# ReboostV2_CAN.net
KiCad netlist of a schematic drawn in Altium Designer
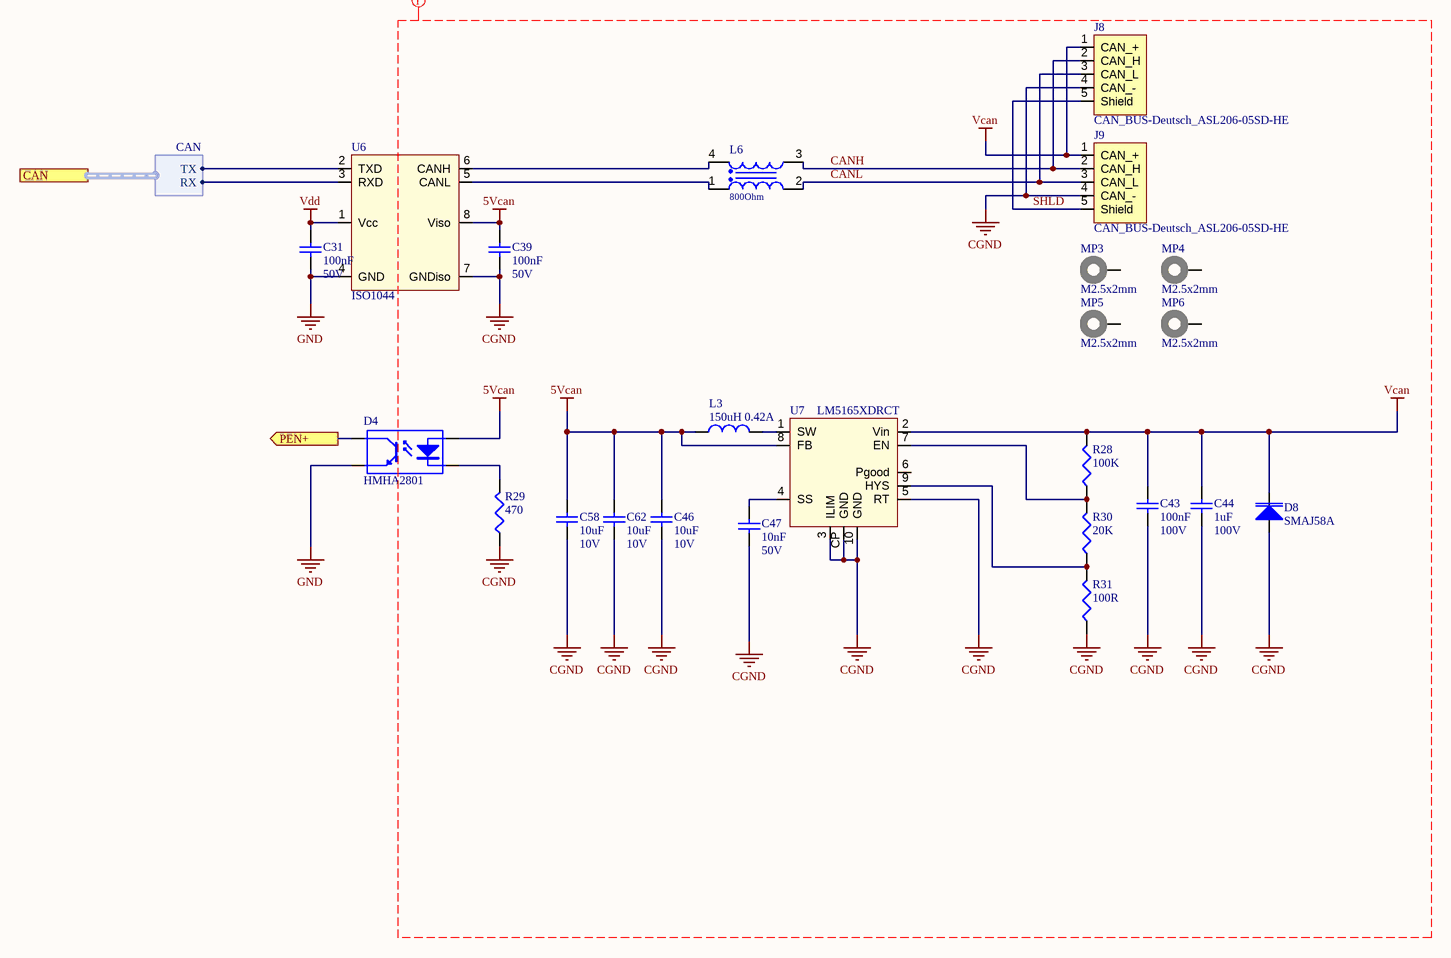
[diagram p0: ReboostV2_CAN.SchDoc]

(export (version "E")
  (design (tool "Eeschema 10.0.6"))
  (components
    (comp (ref "C31")
      (value "100nF")
      (footprint "C0603")
      (description "Capacitor, 100nF, 50V, X7R")
      (fields (field (name "VOLTAGE RATING") "50V"))
      (libsource (lib "AR_Capacitors_Ceramic") (part "100nF/0603/CER/50V"))
    )
    (comp (ref "C39")
      (value "100nF")
      (footprint "C0603")
      (description "Capacitor, 100nF, 50V, X7R")
      (fields (field (name "VOLTAGE RATING") "50V"))
      (libsource (lib "AR_Capacitors_Ceramic") (part "100nF/0603/CER/50V"))
    )
    (comp (ref "C43")
      (value "100nF")
      (footprint "C-0805")
      (description "Capacitor, 100nF, 100V, X7R")
      (fields (field (name "VOLTAGE RATING") "100V"))
      (libsource (lib "AR_Capacitors_Ceramic") (part "100nF/0805/CER/100V"))
    )
    (comp (ref "C44")
      (value "1uF")
      (footprint "C-1206")
      (description "Capacitor, 1uF, 100V, X7R")
      (fields (field (name "VOLTAGE RATING") "100V"))
      (libsource (lib "AR_Capacitors_Ceramic") (part "1uF/1206/CER/100V"))
    )
    (comp (ref "C46")
      (value "10uF")
      (footprint "C-0805")
      (description "Capacitor, 10uF, 10V, X7R")
      (fields (field (name "VOLTAGE RATING") "10V"))
      (libsource (lib "AR_Capacitors_Ceramic") (part "10uF/0805/CER/10V"))
    )
    (comp (ref "C47")
      (value "10nF")
      (footprint "C0603")
      (description "Capacitor, 10nF, 50V, X7R")
      (fields (field (name "VOLTAGE RATING") "50V"))
      (libsource (lib "AR_Capacitors_Ceramic") (part "10nF/0603/CER/50V"))
    )
    (comp (ref "C58")
      (value "10uF")
      (footprint "C-0805")
      (description "Capacitor, 10uF, 10V, X7R")
      (fields (field (name "VOLTAGE RATING") "10V"))
      (libsource (lib "AR_Capacitors_Ceramic") (part "10uF/0805/CER/10V"))
    )
    (comp (ref "C62")
      (value "10uF")
      (footprint "C-0805")
      (description "Capacitor, 10uF, 10V, X7R")
      (fields (field (name "VOLTAGE RATING") "10V"))
      (libsource (lib "AR_Capacitors_Ceramic") (part "10uF/0805/CER/10V"))
    )
    (comp (ref "D4")
      (value "HMHA2801")
      (footprint "FSOP4")
      (description "Optocoupler, Vout:80V, Iin:0.01A")
      (libsource (lib "AR_Optocouplers") (part "HMHA2801"))
    )
    (comp (ref "D8")
      (value "SMAJ58A")
      (footprint "SMA")
      (description "Diode TVS, Vrwm: 58V, Vbr: 71.2V, Vc: 93.6V, Ippm: 4.3A")
      (libsource (lib "AR_Diodes") (part "SMAJ58A"))
    )
    (comp (ref "J8")
      (value "CAN_BUS-Deutsch_ASL206-05SD-HE")
      (footprint "ASL206-05SD-HE")
      (libsource (lib "Top Dutch Solar Racing") (part "CAN_BUS-Deutsch_ASL206-05SD-HE"))
    )
    (comp (ref "J9")
      (value "CAN_BUS-Deutsch_ASL206-05SD-HE")
      (footprint "ASL206-05SD-HE")
      (libsource (lib "Top Dutch Solar Racing") (part "CAN_BUS-Deutsch_ASL206-05SD-HE"))
    )
    (comp (ref "L3")
      (value "150uH 0.42A")
      (footprint "WE-TPC 4828, MH")
      (description "150UH, 30%, 0.42A")
      (libsource (lib "AR_Inductors") (part "744043151"))
    )
    (comp (ref "L6")
      (value "800Ohm")
      (footprint "WE-CNSW_1812")
      (description "WE-CNSW SMT Common Mode Line Filter, size 1812, 800Ohm, 1A, 60V")
      (fields
        (field (name "MANUFACTURER PART NUMBER") "744235801")
        (field (name "MANUFACTURER") "Wurth Elektronik")
      )
      (libsource (lib "WE-CNSW (rev20a)") (part "744235801"))
    )
    (comp (ref "MP3")
      (value "M2.5x2mm")
      (footprint "9774020151")
      (description "WA-SMSI SMT Steel Spacer, M2.5 Thread Internal, OD 5.1mm, M2.5x2mm")
      (fields
        (field (name "MANUFACTURER PART NUMBER") "9774020151")
        (field (name "MANUFACTURER") "Wurth Elektronik")
      )
      (libsource (lib "Altium_SMSI (rev20c)") (part "9774020151"))
    )
    (comp (ref "MP4")
      (value "M2.5x2mm")
      (footprint "9774020151")
      (description "WA-SMSI SMT Steel Spacer, M2.5 Thread Internal, OD 5.1mm, M2.5x2mm")
      (fields
        (field (name "MANUFACTURER PART NUMBER") "9774020151")
        (field (name "MANUFACTURER") "Wurth Elektronik")
      )
      (libsource (lib "Altium_SMSI (rev20c)") (part "9774020151"))
    )
    (comp (ref "MP5")
      (value "M2.5x2mm")
      (footprint "9774020151")
      (description "WA-SMSI SMT Steel Spacer, M2.5 Thread Internal, OD 5.1mm, M2.5x2mm")
      (fields
        (field (name "MANUFACTURER PART NUMBER") "9774020151")
        (field (name "MANUFACTURER") "Wurth Elektronik")
      )
      (libsource (lib "Altium_SMSI (rev20c)") (part "9774020151"))
    )
    (comp (ref "MP6")
      (value "M2.5x2mm")
      (footprint "9774020151")
      (description "WA-SMSI SMT Steel Spacer, M2.5 Thread Internal, OD 5.1mm, M2.5x2mm")
      (fields
        (field (name "MANUFACTURER PART NUMBER") "9774020151")
        (field (name "MANUFACTURER") "Wurth Elektronik")
      )
      (libsource (lib "Altium_SMSI (rev20c)") (part "9774020151"))
    )
    (comp (ref "R28")
      (value "100K")
      (footprint "0603")
      (description "Resistor, 100K, 1%, 0.063W, 50V, 100PPM, 0603")
      (libsource (lib "AR_Resistors_SMD") (part "100K/0603/0063W/50V"))
    )
    (comp (ref "R29")
      (value "470")
      (footprint "0603")
      (description "Resistor, 470, 1%, 0.063W, 50V, 100PPM, 0603")
      (libsource (lib "AR_Resistors_SMD") (part "470/0603/0063W/50V"))
    )
    (comp (ref "R30")
      (value "20K")
      (footprint "0603")
      (description "Resistor, 20K, 1%, 0.063W, 50V, 100PPM, 0603")
      (libsource (lib "AR_Resistors_SMD") (part "20K/0603/0063W/50V"))
    )
    (comp (ref "R31")
      (value "100R")
      (footprint "0603")
      (description "Resistor, 100R, 1%, 0.063W, 50V, 200PPM, 0603")
      (libsource (lib "AR_Resistors_SMD") (part "100/0603/0063W/50V"))
    )
    (comp (ref "U6")
      (value "ISO1044")
      (footprint "SO-8")
      (description "ISO1044 Isolated CAN FD Transceiver in Small Package")
      (libsource (lib "AR_ICs") (part "ISO1044"))
    )
    (comp (ref "U7")
      (value "LM5165XDRCT")
      (footprint "PWSON10")
      (description "Buck Vreg 150mA 5Vout 5-65Vin")
      (libsource (lib "AR_Vreg") (part "LM5165X"))
    )
  )
  (nets
    (net (code "2") (name "/CANH") (class "Default")
      (node (ref "J8") (pin "2") (pinfunction "CAN_H_2") (pintype "passive"))
      (node (ref "J9") (pin "2") (pinfunction "CAN_H_2") (pintype "passive"))
      (node (ref "L6") (pin "3") (pinfunction "3_3") (pintype "passive"))
    )
    (net (code "3") (name "/CANL") (class "Default")
      (node (ref "J8") (pin "3") (pinfunction "CAN_L_3") (pintype "passive"))
      (node (ref "J9") (pin "3") (pinfunction "CAN_L_3") (pintype "passive"))
      (node (ref "L6") (pin "2") (pinfunction "2_2") (pintype "passive"))
    )
    (net (code "4") (name "/PEN+") (class "Default")
      (node (ref "D4") (pin "4") (pinfunction "C1_4") (pintype "passive"))
    )
    (net (code "5") (name "/RX") (class "Default")
      (node (ref "U6") (pin "3") (pinfunction "RXD_3") (pintype "passive"))
    )
    (net (code "6") (name "/SHLD") (class "Default")
      (node (ref "J8") (pin "5") (pinfunction "Shield_5") (pintype "passive"))
      (node (ref "J9") (pin "5") (pinfunction "Shield_5") (pintype "passive"))
    )
    (net (code "7") (name "/TX") (class "Default")
      (node (ref "U6") (pin "2") (pinfunction "TXD_2") (pintype "passive"))
    )
    (net (code "9") (name "5Vcan") (class "Default")
      (node (ref "C39") (pin "2") (pinfunction "2_2") (pintype "passive"))
      (node (ref "C46") (pin "2") (pinfunction "2_2") (pintype "passive"))
      (node (ref "C58") (pin "2") (pinfunction "2_2") (pintype "passive"))
      (node (ref "C62") (pin "2") (pinfunction "2_2") (pintype "passive"))
      (node (ref "D4") (pin "1") (pinfunction "A1_1") (pintype "passive"))
      (node (ref "L3") (pin "2") (pinfunction "2_2") (pintype "passive"))
      (node (ref "U6") (pin "8") (pinfunction "Viso_8") (pintype "passive"))
      (node (ref "U7") (pin "8") (pinfunction "FB_8") (pintype "passive"))
    )
    (net (code "10") (name "CGND") (class "Default")
      (node (ref "C39") (pin "1") (pinfunction "1_1") (pintype "passive"))
      (node (ref "C43") (pin "1") (pinfunction "1_1") (pintype "passive"))
      (node (ref "C44") (pin "1") (pinfunction "1_1") (pintype "passive"))
      (node (ref "C46") (pin "1") (pinfunction "1_1") (pintype "passive"))
      (node (ref "C47") (pin "1") (pinfunction "1_1") (pintype "passive"))
      (node (ref "C58") (pin "1") (pinfunction "1_1") (pintype "passive"))
      (node (ref "C62") (pin "1") (pinfunction "1_1") (pintype "passive"))
      (node (ref "D8") (pin "1") (pinfunction "1_1") (pintype "passive"))
      (node (ref "J8") (pin "4") (pinfunction "CAN_-_4") (pintype "passive"))
      (node (ref "J9") (pin "4") (pinfunction "CAN_-_4") (pintype "passive"))
      (node (ref "R29") (pin "1") (pinfunction "1_1") (pintype "passive"))
      (node (ref "R31") (pin "1") (pinfunction "1_1") (pintype "passive"))
      (node (ref "U6") (pin "7") (pinfunction "GNDiso_7") (pintype "passive"))
      (node (ref "U7") (pin "10") (pinfunction "GND_10") (pintype "passive"))
      (node (ref "U7") (pin "3") (pinfunction "ILIM_3") (pintype "passive"))
      (node (ref "U7") (pin "5") (pinfunction "RT_5") (pintype "passive"))
      (node (ref "U7") (pin "CP") (pinfunction "GND_CP") (pintype "passive"))
    )
    (net (code "11") (name "GND") (class "Default")
      (node (ref "C31") (pin "1") (pinfunction "1_1") (pintype "passive"))
      (node (ref "D4") (pin "3") (pinfunction "E1_3") (pintype "passive"))
      (node (ref "U6") (pin "4") (pinfunction "GND_4") (pintype "passive"))
    )
    (net (code "12") (name "Net-(D4-K1)") (class "Default")
      (node (ref "D4") (pin "2") (pinfunction "K1_2") (pintype "passive"))
      (node (ref "R29") (pin "2") (pinfunction "2_2") (pintype "passive"))
    )
    (net (code "13") (name "Net-(U6-CANH)") (class "Default")
      (node (ref "L6") (pin "4") (pinfunction "4_4") (pintype "passive"))
      (node (ref "U6") (pin "6") (pinfunction "CANH_6") (pintype "passive"))
    )
    (net (code "14") (name "Net-(U6-CANL)") (class "Default")
      (node (ref "L6") (pin "1") (pinfunction "1_1") (pintype "passive"))
      (node (ref "U6") (pin "5") (pinfunction "CANL_5") (pintype "passive"))
    )
    (net (code "15") (name "Net-(U7-EN)") (class "Default")
      (node (ref "R28") (pin "1") (pinfunction "1_1") (pintype "passive"))
      (node (ref "R30") (pin "2") (pinfunction "2_2") (pintype "passive"))
      (node (ref "U7") (pin "7") (pinfunction "EN_7") (pintype "passive"))
    )
    (net (code "16") (name "Net-(U7-HYS)") (class "Default")
      (node (ref "R30") (pin "1") (pinfunction "1_1") (pintype "passive"))
      (node (ref "R31") (pin "2") (pinfunction "2_2") (pintype "passive"))
      (node (ref "U7") (pin "9") (pinfunction "HYS_9") (pintype "passive"))
    )
    (net (code "17") (name "Net-(U7-SS)") (class "Default")
      (node (ref "C47") (pin "2") (pinfunction "2_2") (pintype "passive"))
      (node (ref "U7") (pin "4") (pinfunction "SS_4") (pintype "passive"))
    )
    (net (code "18") (name "Net-(U7-SW)") (class "Default")
      (node (ref "L3") (pin "1") (pinfunction "1_1") (pintype "passive"))
      (node (ref "U7") (pin "1") (pinfunction "SW_1") (pintype "passive"))
    )
    (net (code "19") (name "Vcan") (class "Default")
      (node (ref "C43") (pin "2") (pinfunction "2_2") (pintype "passive"))
      (node (ref "C44") (pin "2") (pinfunction "2_2") (pintype "passive"))
      (node (ref "D8") (pin "2") (pinfunction "2_2") (pintype "passive"))
      (node (ref "J8") (pin "1") (pinfunction "CAN_+_1") (pintype "passive"))
      (node (ref "J9") (pin "1") (pinfunction "CAN_+_1") (pintype "passive"))
      (node (ref "R28") (pin "2") (pinfunction "2_2") (pintype "passive"))
      (node (ref "U7") (pin "2") (pinfunction "Vin_2") (pintype "passive"))
    )
    (net (code "20") (name "Vdd") (class "Default")
      (node (ref "C31") (pin "2") (pinfunction "2_2") (pintype "passive"))
      (node (ref "U6") (pin "1") (pinfunction "Vcc_1") (pintype "passive"))
    )
    (net (code "21") (name "unconnected-(MP3-Pad1)") (class "Default")
      (node (ref "MP3") (pin "1") (pinfunction "1_1") (pintype "passive"))
    )
    (net (code "22") (name "unconnected-(MP4-Pad1)") (class "Default")
      (node (ref "MP4") (pin "1") (pinfunction "1_1") (pintype "passive"))
    )
    (net (code "23") (name "unconnected-(MP5-Pad1)") (class "Default")
      (node (ref "MP5") (pin "1") (pinfunction "1_1") (pintype "passive"))
    )
    (net (code "24") (name "unconnected-(MP6-Pad1)") (class "Default")
      (node (ref "MP6") (pin "1") (pinfunction "1_1") (pintype "passive"))
    )
    (net (code "25") (name "unconnected-(U7-Pgood-Pad6)") (class "Default")
      (node (ref "U7") (pin "6") (pinfunction "Pgood_6") (pintype "passive"))
    )
  )
)
